# FPGA_SPI_interface.net
KiCad netlist of a schematic drawn in Altium Designer
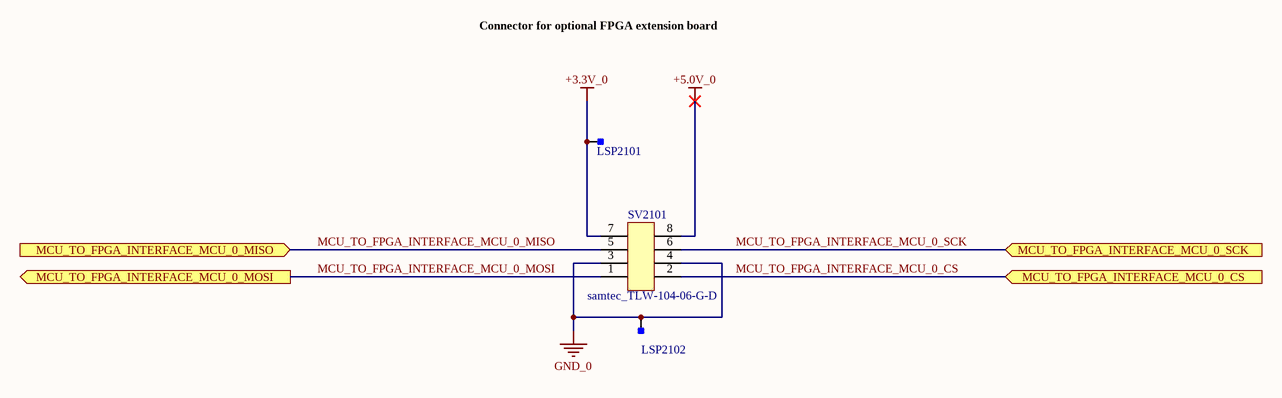
[diagram p0: FPGA_SPI_interface.SchDoc]

(export (version "E")
  (design (tool "Eeschema 10.0.6"))
  (components
    (comp (ref "LSP2101")
      (value "Testpoint_Square")
      (footprint "Testpoint_S1")
      (description "Testpoint, square")
      (libsource (lib "OE750") (part "Testpoint_Square"))
    )
    (comp (ref "LSP2102")
      (value "Testpoint_Square")
      (footprint "Testpoint_S1")
      (description "Testpoint, square")
      (libsource (lib "OE750") (part "Testpoint_Square"))
    )
    (comp (ref "SV2101")
      (value "samtec_TLW-104-06-G-D")
      (footprint "Pinheader_2.54_2x4")
      (fields (field (name "MANUFACTURER") "Samtec"))
      (libsource (lib "OE750") (part "X2x4"))
    )
  )
  (nets
    (net (code "1") (name "+3.3V_0") (class "Default")
      (node (ref "LSP2101") (pin "1") (pinfunction "1_1") (pintype "passive"))
      (node (ref "SV2101") (pin "7") (pintype "passive"))
    )
    (net (code "2") (name "+5.0V_0") (class "Default") (node (ref "SV2101") (pin "8") (pintype "passive")))
    (net (code "3") (name "/MCU_TO_FPGA_INTERFACE_MCU_0_CS") (class "Default")
      (node (ref "SV2101") (pin "2") (pintype "passive"))
    )
    (net (code "4") (name "/MCU_TO_FPGA_INTERFACE_MCU_0_MISO") (class "Default")
      (node (ref "SV2101") (pin "5") (pintype "passive"))
    )
    (net (code "5") (name "/MCU_TO_FPGA_INTERFACE_MCU_0_MOSI") (class "Default")
      (node (ref "SV2101") (pin "1") (pintype "passive"))
    )
    (net (code "6") (name "/MCU_TO_FPGA_INTERFACE_MCU_0_SCK") (class "Default")
      (node (ref "SV2101") (pin "6") (pintype "passive"))
    )
    (net (code "7") (name "GND_0") (class "Default")
      (node (ref "LSP2102") (pin "1") (pinfunction "1_1") (pintype "passive"))
      (node (ref "SV2101") (pin "3") (pintype "passive"))
      (node (ref "SV2101") (pin "4") (pintype "passive"))
    )
  )
)
